# 09_MRAM_RTC_WDT.net
KiCad netlist of a schematic drawn in Altium Designer
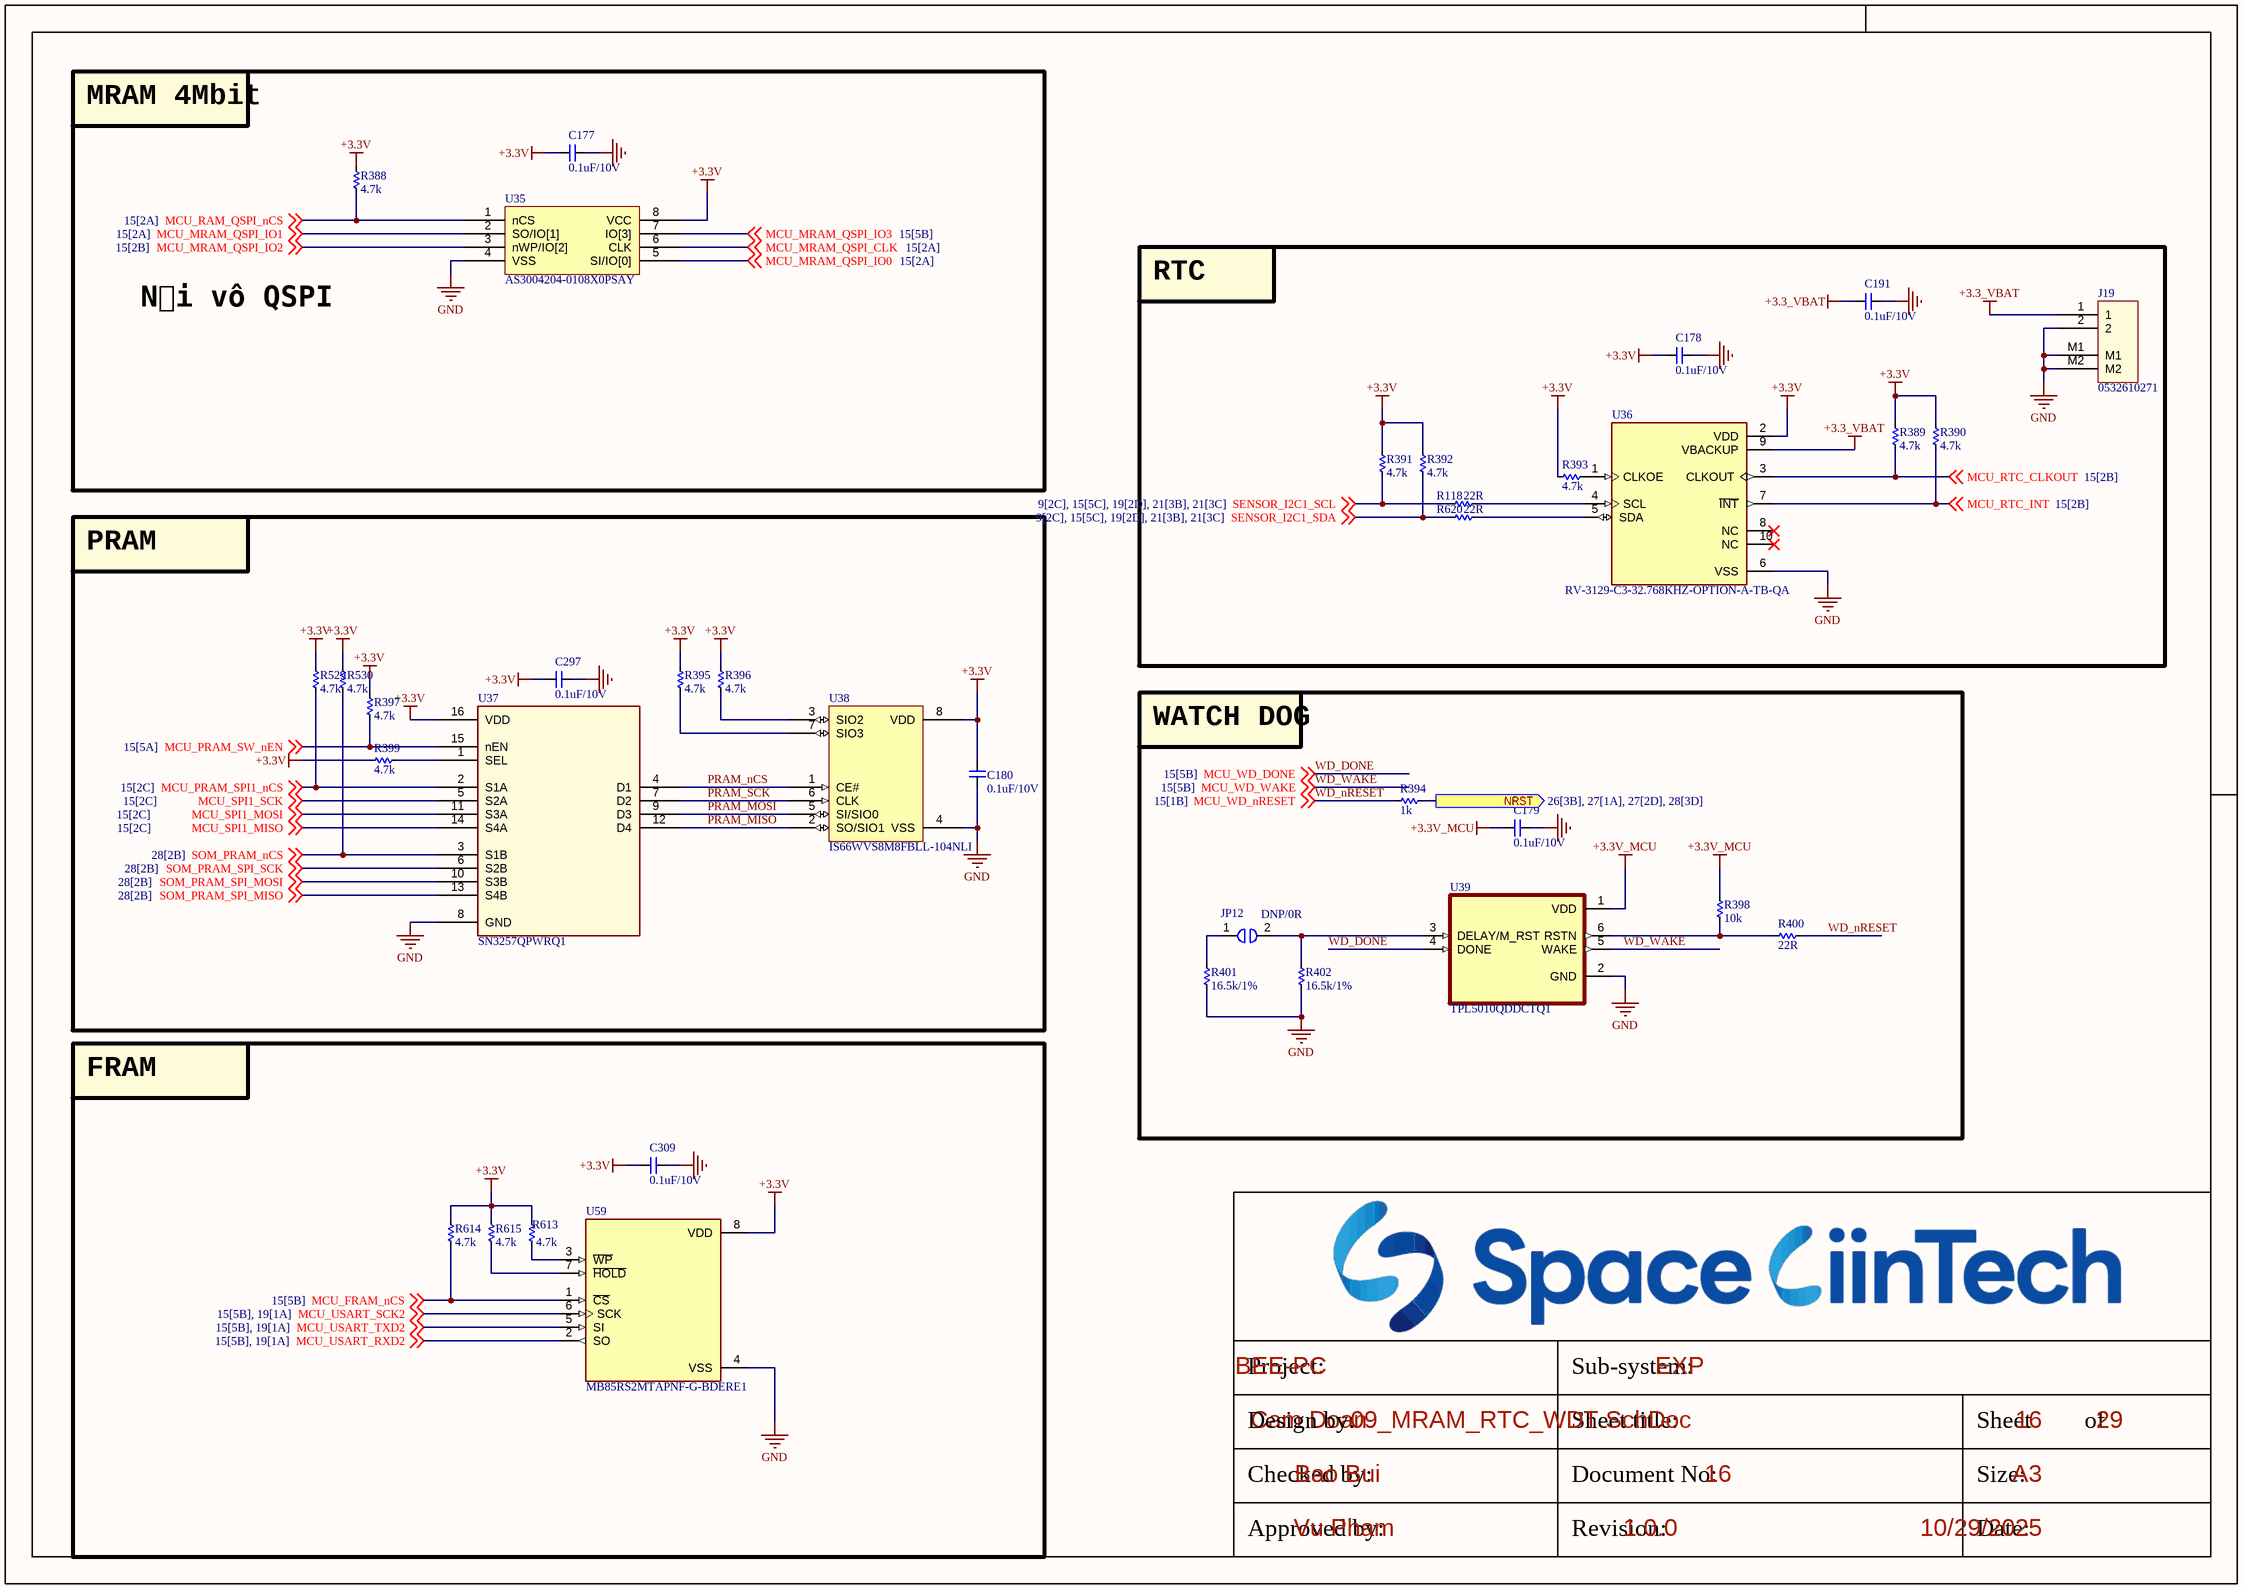
[diagram p0: 09_MRAM_RTC_WDT.SchDoc]

(export (version "E")
  (design (tool "Eeschema 10.0.6"))
  (components
    (comp (ref "C177")
      (value "0.1uF/10V")
      (footprint "CAP_C_1005X60")
      (description "CAP CHIP")
      (libsource (lib "LABLIB") (part "_CAP_C_2"))
    )
    (comp (ref "C178")
      (value "0.1uF/10V")
      (footprint "CAP_C_1005X60")
      (description "CAP CHIP")
      (libsource (lib "LABLIB") (part "_CAP_C_2"))
    )
    (comp (ref "C179")
      (value "0.1uF/10V")
      (footprint "CAP_C_1005X60")
      (description "CAP CHIP")
      (libsource (lib "LABLIB") (part "_CAP_C_2"))
    )
    (comp (ref "C180")
      (value "0.1uF/10V")
      (footprint "CAP_C_1005X60")
      (description "CAP CHIP")
      (libsource (lib "LABLIB") (part "_CAP_C_2"))
    )
    (comp (ref "C191")
      (value "0.1uF/10V")
      (footprint "CAP_C_1005X60")
      (description "CAP CHIP")
      (libsource (lib "LABLIB") (part "_CAP_C_2"))
    )
    (comp (ref "C297")
      (value "0.1uF/10V")
      (footprint "CAP_C_1005X60")
      (description "CAP CHIP")
      (libsource (lib "LABLIB") (part "_CAP_C_2"))
    )
    (comp (ref "C309")
      (value "0.1uF/10V")
      (footprint "CAP_C_1005X60")
      (description "CAP CHIP")
      (libsource (lib "LABLIB") (part "_CAP_C_2"))
    )
    (comp (ref "J19")
      (value "0532610271")
      (footprint "MOLEX_0532610271")
      (libsource (lib "LABLIB") (part "Header 2x1_2M"))
    )
    (comp (ref "JP12")
      (value "DNP/0R")
      (footprint "RES_C_1608X60")
      (libsource (lib "LABLIB") (part "JUMPER_1_1"))
    )
    (comp (ref "R118")
      (value "22R")
      (footprint "RES_C_1005X40")
      (description "RES")
      (libsource (lib "LABLIB") (part "_RES_B_2"))
    )
    (comp (ref "R388")
      (value "4.7k")
      (footprint "RES_C_1005X40")
      (description "RES")
      (libsource (lib "LABLIB") (part "_RES_B_2"))
    )
    (comp (ref "R389")
      (value "4.7k")
      (footprint "RES_C_1005X40")
      (description "RES")
      (libsource (lib "LABLIB") (part "_RES_B_2"))
    )
    (comp (ref "R390")
      (value "4.7k")
      (footprint "RES_C_1005X40")
      (description "RES")
      (libsource (lib "LABLIB") (part "_RES_B_2"))
    )
    (comp (ref "R391")
      (value "4.7k")
      (footprint "RES_C_1005X40")
      (description "RES")
      (libsource (lib "LABLIB") (part "_RES_B_2"))
    )
    (comp (ref "R392")
      (value "4.7k")
      (footprint "RES_C_1005X40")
      (description "RES")
      (libsource (lib "LABLIB") (part "_RES_B_2"))
    )
    (comp (ref "R393")
      (value "4.7k")
      (footprint "RES_C_1005X40")
      (description "RES")
      (libsource (lib "LABLIB") (part "_RES_B_2"))
    )
    (comp (ref "R394")
      (value "1k")
      (footprint "RES_C_1005X40")
      (description "RES")
      (libsource (lib "LABLIB") (part "_RES_B_2"))
    )
    (comp (ref "R395")
      (value "4.7k")
      (footprint "RES_C_1005X40")
      (description "RES")
      (libsource (lib "LABLIB") (part "_RES_B_2"))
    )
    (comp (ref "R396")
      (value "4.7k")
      (footprint "RES_C_1005X40")
      (description "RES")
      (libsource (lib "LABLIB") (part "_RES_B_2"))
    )
    (comp (ref "R397")
      (value "4.7k")
      (footprint "RES_C_1005X40")
      (description "RES")
      (libsource (lib "LABLIB") (part "_RES_B_2"))
    )
    (comp (ref "R398")
      (value "10k")
      (footprint "RES_C_1005X40")
      (description "RES")
      (libsource (lib "LABLIB") (part "_RES_B_2"))
    )
    (comp (ref "R399")
      (value "4.7k")
      (footprint "RES_C_1005X40")
      (description "RES")
      (libsource (lib "LABLIB") (part "_RES_B_2"))
    )
    (comp (ref "R400")
      (value "22R")
      (footprint "RES_C_1005X40")
      (description "RES")
      (libsource (lib "LABLIB") (part "_RES_B_2"))
    )
    (comp (ref "R401")
      (value "16.5k/1%")
      (footprint "RES_C_1005X40")
      (description "RES")
      (libsource (lib "LABLIB") (part "_RES_B_2"))
    )
    (comp (ref "R402")
      (value "16.5k/1%")
      (footprint "RES_C_1005X40")
      (description "RES")
      (libsource (lib "LABLIB") (part "_RES_B_2"))
    )
    (comp (ref "R529")
      (value "4.7k")
      (footprint "RES_C_1005X40")
      (description "RES")
      (libsource (lib "LABLIB") (part "_RES_B_2"))
    )
    (comp (ref "R530")
      (value "4.7k")
      (footprint "RES_C_1005X40")
      (description "RES")
      (libsource (lib "LABLIB") (part "_RES_B_2"))
    )
    (comp (ref "R613")
      (value "4.7k")
      (footprint "RES_C_1005X40")
      (description "RES")
      (libsource (lib "LABLIB") (part "_RES_B_2"))
    )
    (comp (ref "R614")
      (value "4.7k")
      (footprint "RES_C_1005X40")
      (description "RES")
      (libsource (lib "LABLIB") (part "_RES_B_2"))
    )
    (comp (ref "R615")
      (value "4.7k")
      (footprint "RES_C_1005X40")
      (description "RES")
      (libsource (lib "LABLIB") (part "_RES_B_2"))
    )
    (comp (ref "R620")
      (value "22R")
      (footprint "RES_C_1005X40")
      (description "RES")
      (libsource (lib "LABLIB") (part "_RES_B_2"))
    )
    (comp (ref "U35")
      (value "AS3004204-0108X0PSAY")
      (footprint "SOIC127P790X216-8")
      (libsource (lib "LABLIB") (part "IC_RAM_AS3004204-0108X0PSAY"))
    )
    (comp (ref "U36")
      (value "RV-3129-C3-32.768KHZ-OPTION-A-TB-QA")
      (footprint "IC_RV-3129-C3_32.768KHZ_OPTION_A_TB_QA")
      (description "Real-Time Clock Module, Temperature compensated, in 2.5 x 3.7 mm package")
      (fields (field (name "MF") "Micro Crystal") (field (name "MP") "RV-3129-C3 32.768KHZ OPTION A TB QA"))
      (libsource (lib "RV-3129-C3_32.768KHZ_OPTION_A_TB_QA") (part "RV-3129-C3_32.768KHZ_OPTION_A_TB_QA"))
    )
    (comp (ref "U37")
      (value "SN3257QPWRQ1")
      (footprint "SOIC_PRQ1_TEX")
      (fields (field (name "COPYRIGHT") "Copyright (C) 2025 Ultra Librarian. All rights reserved."))
      (libsource (lib "LABLIB") (part "IC_SW_SPI_SN3257QPWRQ1"))
    )
    (comp (ref "U38")
      (value "IS66WVS8M8FBLL-104NLI")
      (footprint "SOIC8_150MIL_N_ISI")
      (description "No Description Available")
      (fields
        (field (name "MANUFACTURER_PART_NUMBER") "IS66WVS4M8BLL-104NLI")
        (field (name "COPYRIGHT") "Copyright (C) 2025 Ultra Librarian. All rights reserved.")
      )
      (libsource (lib "COMM_SCHLIB") (part "IS66WVS4M8BLL-104NLI"))
    )
    (comp (ref "U39")
      (value "TPL5010QDDCTQ1")
      (footprint "SOT95P280X145-6N")
      (libsource (lib "TPL5010QDDCTQ1") (part "TPL5010QDDCTQ1"))
    )
    (comp (ref "U59")
      (value "MB85RS2MTAPNF-G-BDERE1")
      (footprint "SOIC127P602X173-8N")
      (description "FRAM _Ferroelectric RAM_ Memory IC 2Mb _256K x 8_ SPI 40MHz 8-SOP")
      (fields (field (name "MF") "Fujitsu Electronics") (field (name "DIGI-KEY_PART_NUMBER") "865-1286-1-ND"))
      (libsource (lib "MB85RS2MTAPNF-G-BDERE1") (part "MB85RS2MTAPNF-G-BDERE1"))
    )
  )
  (nets
    (net (code "1") (name "+3.3V") (class "Default")
      (node (ref "C177") (pin "2") (pinfunction "2_2") (pintype "passive"))
      (node (ref "C178") (pin "2") (pinfunction "2_2") (pintype "passive"))
      (node (ref "C180") (pin "1") (pinfunction "1_1") (pintype "passive"))
      (node (ref "C297") (pin "2") (pinfunction "2_2") (pintype "passive"))
      (node (ref "C309") (pin "2") (pinfunction "2_2") (pintype "passive"))
      (node (ref "R388") (pin "2") (pinfunction "2_2") (pintype "passive"))
      (node (ref "R389") (pin "2") (pinfunction "2_2") (pintype "passive"))
      (node (ref "R390") (pin "2") (pinfunction "2_2") (pintype "passive"))
      (node (ref "R391") (pin "2") (pinfunction "2_2") (pintype "passive"))
      (node (ref "R392") (pin "2") (pinfunction "2_2") (pintype "passive"))
      (node (ref "R393") (pin "2") (pinfunction "2_2") (pintype "passive"))
      (node (ref "R395") (pin "2") (pinfunction "2_2") (pintype "passive"))
      (node (ref "R396") (pin "2") (pinfunction "2_2") (pintype "passive"))
      (node (ref "R397") (pin "2") (pinfunction "2_2") (pintype "passive"))
      (node (ref "R399") (pin "2") (pinfunction "2_2") (pintype "passive"))
      (node (ref "R529") (pin "2") (pinfunction "2_2") (pintype "passive"))
      (node (ref "R530") (pin "2") (pinfunction "2_2") (pintype "passive"))
      (node (ref "R613") (pin "2") (pinfunction "2_2") (pintype "passive"))
      (node (ref "R614") (pin "2") (pinfunction "2_2") (pintype "passive"))
      (node (ref "R615") (pin "2") (pinfunction "2_2") (pintype "passive"))
      (node (ref "U35") (pin "8") (pinfunction "VCC_8") (pintype "passive"))
      (node (ref "U36") (pin "2") (pinfunction "VDD_2") (pintype "power_in"))
      (node (ref "U37") (pin "16") (pinfunction "VDD_16") (pintype "passive"))
      (node (ref "U38") (pin "8") (pinfunction "VDD_8") (pintype "power_in"))
      (node (ref "U59") (pin "8") (pinfunction "VDD_8") (pintype "power_in"))
    )
    (net (code "2") (name "+3.3V_MCU") (class "Default")
      (node (ref "C179") (pin "2") (pinfunction "2_2") (pintype "passive"))
      (node (ref "R398") (pin "2") (pinfunction "2_2") (pintype "passive"))
      (node (ref "U39") (pin "1") (pinfunction "VDD_1") (pintype "power_in"))
    )
    (net (code "3") (name "+3.3_VBAT") (class "Default")
      (node (ref "C191") (pin "2") (pinfunction "2_2") (pintype "passive"))
      (node (ref "J19") (pin "1") (pinfunction "1_1") (pintype "passive"))
      (node (ref "U36") (pin "9") (pinfunction "VBACKUP_9") (pintype "power_in"))
    )
    (net (code "4") (name "/NRST") (class "Default")
      (node (ref "R394") (pin "1") (pinfunction "1_1") (pintype "passive"))
    )
    (net (code "5") (name "/PRAM_MISO") (class "Default")
      (node (ref "U37") (pin "12") (pinfunction "D4_12") (pintype "passive"))
      (node (ref "U38") (pin "2") (pinfunction "SO/SIO1_2") (pintype "bidirectional"))
    )
    (net (code "6") (name "/PRAM_MOSI") (class "Default")
      (node (ref "U37") (pin "9") (pinfunction "D3_9") (pintype "passive"))
      (node (ref "U38") (pin "5") (pinfunction "SI/SIO0_5") (pintype "bidirectional"))
    )
    (net (code "7") (name "/PRAM_SCK") (class "Default")
      (node (ref "U37") (pin "7") (pinfunction "D2_7") (pintype "passive"))
      (node (ref "U38") (pin "6") (pinfunction "CLK_6") (pintype "input"))
    )
    (net (code "8") (name "/PRAM_nCS") (class "Default")
      (node (ref "U37") (pin "4") (pinfunction "D1_4") (pintype "passive"))
      (node (ref "U38") (pin "1") (pinfunction "CE#_1") (pintype "input"))
    )
    (net (code "9") (name "GND") (class "Default")
      (node (ref "C177") (pin "1") (pinfunction "1_1") (pintype "passive"))
      (node (ref "C178") (pin "1") (pinfunction "1_1") (pintype "passive"))
      (node (ref "C179") (pin "1") (pinfunction "1_1") (pintype "passive"))
      (node (ref "C180") (pin "2") (pinfunction "2_2") (pintype "passive"))
      (node (ref "C191") (pin "1") (pinfunction "1_1") (pintype "passive"))
      (node (ref "C297") (pin "1") (pinfunction "1_1") (pintype "passive"))
      (node (ref "C309") (pin "1") (pinfunction "1_1") (pintype "passive"))
      (node (ref "J19") (pin "2") (pinfunction "2_2") (pintype "passive"))
      (node (ref "J19") (pin "M1") (pinfunction "M1_M1") (pintype "passive"))
      (node (ref "J19") (pin "M2") (pinfunction "M2_M2") (pintype "passive"))
      (node (ref "R401") (pin "1") (pinfunction "1_1") (pintype "passive"))
      (node (ref "R402") (pin "1") (pinfunction "1_1") (pintype "passive"))
      (node (ref "U35") (pin "4") (pinfunction "VSS_4") (pintype "passive"))
      (node (ref "U36") (pin "6") (pinfunction "VSS_6") (pintype "power_in"))
      (node (ref "U37") (pin "8") (pinfunction "GND_8") (pintype "passive"))
      (node (ref "U38") (pin "4") (pinfunction "VSS_4") (pintype "power_in"))
      (node (ref "U39") (pin "2") (pinfunction "GND_2") (pintype "power_in"))
      (node (ref "U59") (pin "4") (pinfunction "VSS_4") (pintype "power_in"))
    )
    (net (code "10") (name "MCU_FRAM_nCS") (class "Default")
      (node (ref "R614") (pin "1") (pinfunction "1_1") (pintype "passive"))
      (node (ref "U59") (pin "1") (pinfunction "~{CS}_1") (pintype "input"))
    )
    (net (code "11") (name "MCU_MRAM_QSPI_CLK") (class "Default")
      (node (ref "U35") (pin "6") (pinfunction "CLK_6") (pintype "passive"))
    )
    (net (code "12") (name "MCU_MRAM_QSPI_IO0") (class "Default")
      (node (ref "U35") (pin "5") (pinfunction "SI/IO[0]_5") (pintype "passive"))
    )
    (net (code "13") (name "MCU_MRAM_QSPI_IO1") (class "Default")
      (node (ref "U35") (pin "2") (pinfunction "SO/IO[1]_2") (pintype "passive"))
    )
    (net (code "14") (name "MCU_MRAM_QSPI_IO2") (class "Default")
      (node (ref "U35") (pin "3") (pinfunction "nWP/IO[2]_3") (pintype "passive"))
    )
    (net (code "15") (name "MCU_MRAM_QSPI_IO3") (class "Default")
      (node (ref "U35") (pin "7") (pinfunction "IO[3]_7") (pintype "passive"))
    )
    (net (code "16") (name "MCU_PRAM_SPI1_nCS") (class "Default")
      (node (ref "R529") (pin "1") (pinfunction "1_1") (pintype "passive"))
      (node (ref "U37") (pin "2") (pinfunction "S1A_2") (pintype "passive"))
    )
    (net (code "17") (name "MCU_PRAM_SW_nEN") (class "Default")
      (node (ref "R397") (pin "1") (pinfunction "1_1") (pintype "passive"))
      (node (ref "U37") (pin "15") (pinfunction "nEN_15") (pintype "passive"))
    )
    (net (code "18") (name "MCU_RAM_QSPI_nCS") (class "Default")
      (node (ref "R388") (pin "1") (pinfunction "1_1") (pintype "passive"))
      (node (ref "U35") (pin "1") (pinfunction "nCS_1") (pintype "passive"))
    )
    (net (code "19") (name "MCU_RTC_CLKOUT") (class "Default")
      (node (ref "R389") (pin "1") (pinfunction "1_1") (pintype "passive"))
      (node (ref "U36") (pin "3") (pinfunction "CLKOUT_3") (pintype "output"))
    )
    (net (code "20") (name "MCU_RTC_INT") (class "Default")
      (node (ref "R390") (pin "1") (pinfunction "1_1") (pintype "passive"))
      (node (ref "U36") (pin "7") (pinfunction "~{INT}_7") (pintype "output"))
    )
    (net (code "21") (name "MCU_SPI1_MISO") (class "Default")
      (node (ref "U37") (pin "14") (pinfunction "S4A_14") (pintype "passive"))
    )
    (net (code "22") (name "MCU_SPI1_MOSI") (class "Default")
      (node (ref "U37") (pin "11") (pinfunction "S3A_11") (pintype "passive"))
    )
    (net (code "23") (name "MCU_SPI1_SCK") (class "Default")
      (node (ref "U37") (pin "5") (pinfunction "S2A_5") (pintype "passive"))
    )
    (net (code "24") (name "MCU_USART_RXD2") (class "Default")
      (node (ref "U59") (pin "2") (pinfunction "SO_2") (pintype "output"))
    )
    (net (code "25") (name "MCU_USART_SCK2") (class "Default")
      (node (ref "U59") (pin "6") (pinfunction "SCK_6") (pintype "input"))
    )
    (net (code "26") (name "MCU_USART_TXD2") (class "Default")
      (node (ref "U59") (pin "5") (pinfunction "SI_5") (pintype "input"))
    )
    (net (code "27") (name "MCU_WD_DONE") (class "Default")
      (node (ref "U39") (pin "4") (pinfunction "DONE_4") (pintype "input"))
    )
    (net (code "28") (name "MCU_WD_WAKE") (class "Default")
      (node (ref "U39") (pin "5") (pinfunction "WAKE_5") (pintype "output"))
    )
    (net (code "29") (name "MCU_WD_nRESET") (class "Default")
      (node (ref "R394") (pin "2") (pinfunction "2_2") (pintype "passive"))
      (node (ref "R400") (pin "1") (pinfunction "1_1") (pintype "passive"))
    )
    (net (code "30") (name "Net-(JP12-Pad1)") (class "Default")
      (node (ref "JP12") (pin "1") (pinfunction "1_1") (pintype "passive"))
      (node (ref "R401") (pin "2") (pinfunction "2_2") (pintype "passive"))
    )
    (net (code "31") (name "Net-(U36-CLKOE)") (class "Default")
      (node (ref "R393") (pin "1") (pinfunction "1_1") (pintype "passive"))
      (node (ref "U36") (pin "1") (pinfunction "CLKOE_1") (pintype "input"))
    )
    (net (code "32") (name "Net-(U36-SCL)") (class "Default")
      (node (ref "R118") (pin "2") (pinfunction "2_2") (pintype "passive"))
      (node (ref "U36") (pin "4") (pinfunction "SCL_4") (pintype "input"))
    )
    (net (code "33") (name "Net-(U36-SDA)") (class "Default")
      (node (ref "R620") (pin "2") (pinfunction "2_2") (pintype "passive"))
      (node (ref "U36") (pin "5") (pinfunction "SDA_5") (pintype "bidirectional"))
    )
    (net (code "34") (name "Net-(U37-SEL)") (class "Default")
      (node (ref "R399") (pin "1") (pinfunction "1_1") (pintype "passive"))
      (node (ref "U37") (pin "1") (pinfunction "SEL_1") (pintype "passive"))
    )
    (net (code "35") (name "Net-(U38-SIO2)") (class "Default")
      (node (ref "R396") (pin "1") (pinfunction "1_1") (pintype "passive"))
      (node (ref "U38") (pin "3") (pinfunction "SIO2_3") (pintype "bidirectional"))
    )
    (net (code "36") (name "Net-(U38-SIO3)") (class "Default")
      (node (ref "R395") (pin "1") (pinfunction "1_1") (pintype "passive"))
      (node (ref "U38") (pin "7") (pinfunction "SIO3_7") (pintype "bidirectional"))
    )
    (net (code "37") (name "Net-(U39-DELAY{slash}M_RST)") (class "Default")
      (node (ref "JP12") (pin "2") (pinfunction "2_2") (pintype "passive"))
      (node (ref "R402") (pin "2") (pinfunction "2_2") (pintype "passive"))
      (node (ref "U39") (pin "3") (pinfunction "DELAY/M_RST_3") (pintype "input"))
    )
    (net (code "38") (name "Net-(U39-RSTN)") (class "Default")
      (node (ref "R398") (pin "1") (pinfunction "1_1") (pintype "passive"))
      (node (ref "R400") (pin "2") (pinfunction "2_2") (pintype "passive"))
      (node (ref "U39") (pin "6") (pinfunction "RSTN_6") (pintype "output"))
    )
    (net (code "39") (name "Net-(U59-~{HOLD})") (class "Default")
      (node (ref "R615") (pin "1") (pinfunction "1_1") (pintype "passive"))
      (node (ref "U59") (pin "7") (pinfunction "~{HOLD}_7") (pintype "input"))
    )
    (net (code "40") (name "Net-(U59-~{WP})") (class "Default")
      (node (ref "R613") (pin "1") (pinfunction "1_1") (pintype "passive"))
      (node (ref "U59") (pin "3") (pinfunction "~{WP}_3") (pintype "input"))
    )
    (net (code "41") (name "SENSOR_I2C1_SCL") (class "Default")
      (node (ref "R118") (pin "1") (pinfunction "1_1") (pintype "passive"))
      (node (ref "R391") (pin "1") (pinfunction "1_1") (pintype "passive"))
    )
    (net (code "42") (name "SENSOR_I2C1_SDA") (class "Default")
      (node (ref "R392") (pin "1") (pinfunction "1_1") (pintype "passive"))
      (node (ref "R620") (pin "1") (pinfunction "1_1") (pintype "passive"))
    )
    (net (code "43") (name "SOM_PRAM_SPI_MISO") (class "Default")
      (node (ref "U37") (pin "13") (pinfunction "S4B_13") (pintype "passive"))
    )
    (net (code "44") (name "SOM_PRAM_SPI_MOSI") (class "Default")
      (node (ref "U37") (pin "10") (pinfunction "S3B_10") (pintype "passive"))
    )
    (net (code "45") (name "SOM_PRAM_SPI_SCK") (class "Default")
      (node (ref "U37") (pin "6") (pinfunction "S2B_6") (pintype "passive"))
    )
    (net (code "46") (name "SOM_PRAM_nCS") (class "Default")
      (node (ref "R530") (pin "1") (pinfunction "1_1") (pintype "passive"))
      (node (ref "U37") (pin "3") (pinfunction "S1B_3") (pintype "passive"))
    )
    (net (code "47") (name "unconnected-(U36-NC-Pad8)") (class "Default")
      (node (ref "U36") (pin "8") (pinfunction "NC_8") (pintype "passive+no_connect"))
    )
    (net (code "48") (name "unconnected-(U36-NC-Pad10)") (class "Default")
      (node (ref "U36") (pin "10") (pinfunction "NC_10") (pintype "passive+no_connect"))
    )
  )
)
